# MCU.net
KiCad netlist of a schematic drawn in Altium Designer
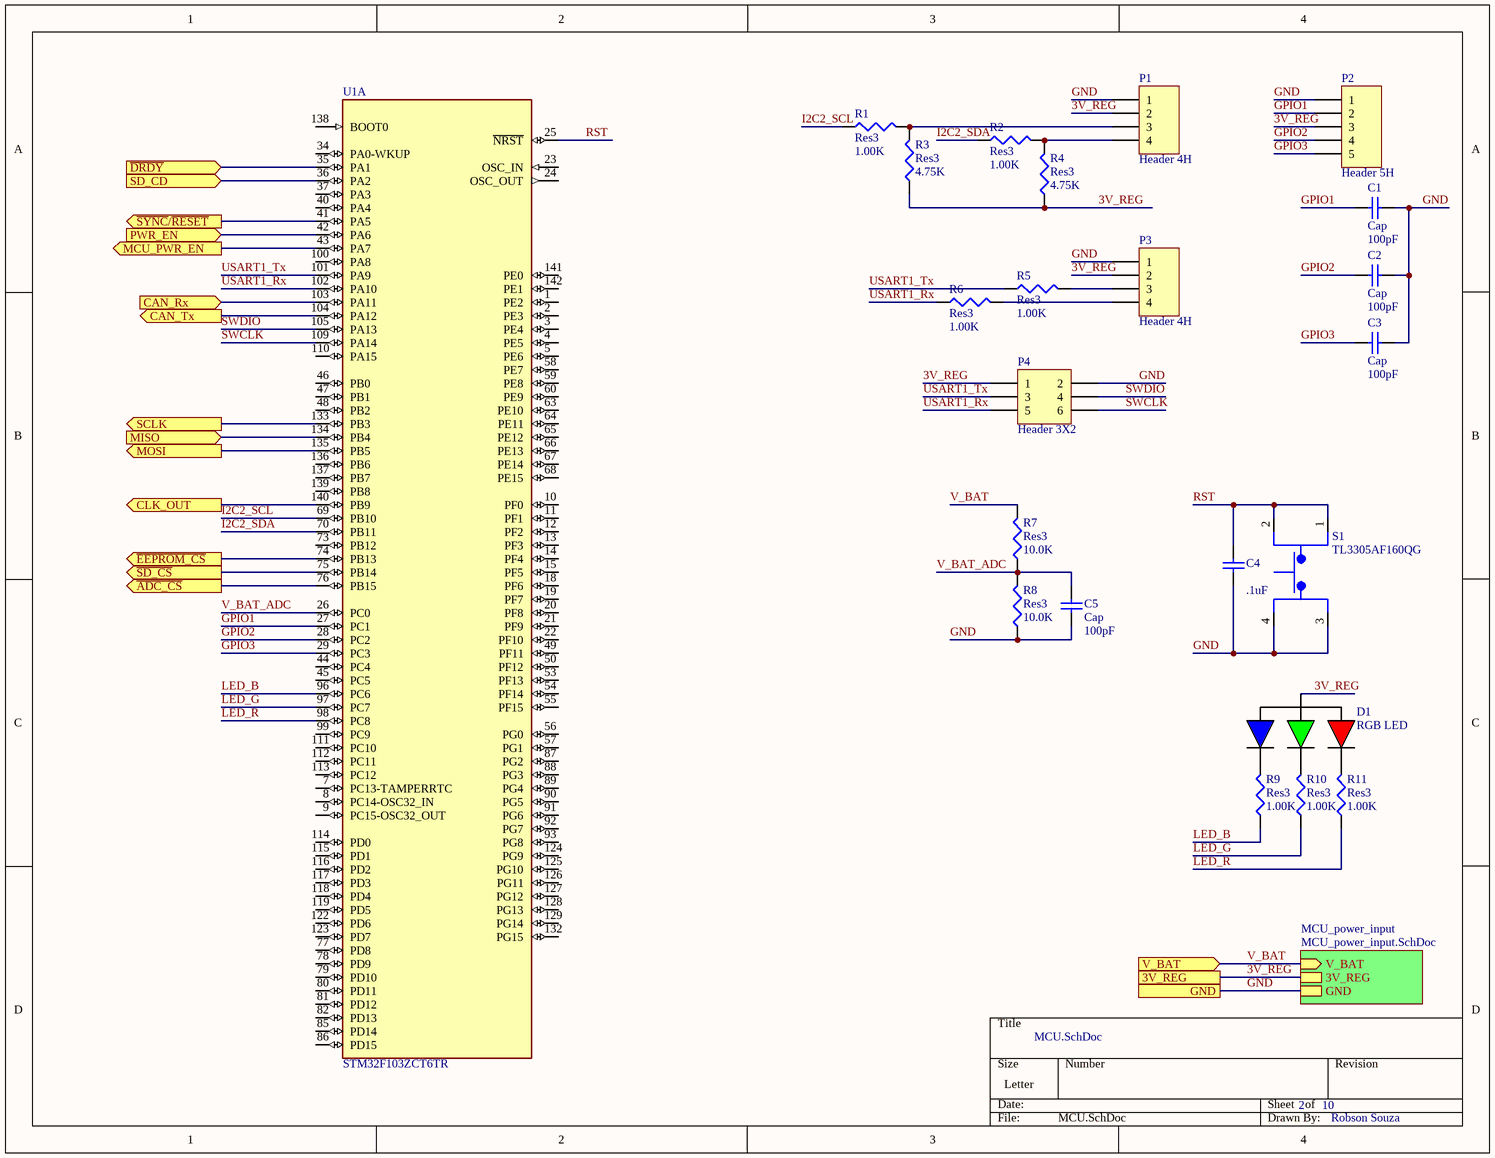
[diagram p0: MCU.SchDoc]

(export (version "E")
  (design (tool "Eeschema 10.0.6"))
  (components
    (comp (ref "C1")
      (value "Cap")
      (footprint "CAPC2012X09M")
      (description "CAP CER 100pF 500v COG 0805")
      (fields
        (field (name "ALTIUM_VALUE") "100pF")
        (field (name "TOLERANCE") "±5%")
        (field (name "MPN") "C0805C101JCGACTU")
      )
      (libsource (lib "esd_library") (part "CAP-COG-100pF-500V-±5%"))
    )
    (comp (ref "C2")
      (value "Cap")
      (footprint "CAPC2012X09M")
      (description "CAP CER 100pF 500v COG 0805")
      (fields
        (field (name "ALTIUM_VALUE") "100pF")
        (field (name "TOLERANCE") "±5%")
        (field (name "MPN") "C0805C101JCGACTU")
      )
      (libsource (lib "esd_library") (part "CAP-COG-100pF-500V-±5%"))
    )
    (comp (ref "C3")
      (value "Cap")
      (footprint "CAPC2012X09M")
      (description "CAP CER 100pF 500v COG 0805")
      (fields
        (field (name "ALTIUM_VALUE") "100pF")
        (field (name "TOLERANCE") "±5%")
        (field (name "MPN") "C0805C101JCGACTU")
      )
      (libsource (lib "esd_library") (part "CAP-COG-100pF-500V-±5%"))
    )
    (comp (ref "C4")
      (value ".1uF")
      (footprint "CAPC2012X09M")
      (description "CAP CER 50v X7R 0805")
      (fields (field (name "TOLERANCE") "±5%") (field (name "MPN") "C0805C104J5RACTU"))
      (libsource (lib "esd_library") (part "CAP-X7R-.1uF-50V-±5%"))
    )
    (comp (ref "C5")
      (value "Cap")
      (footprint "CAPC2012X09M")
      (description "CAP CER 100pF 500v COG 0805")
      (fields
        (field (name "ALTIUM_VALUE") "100pF")
        (field (name "TOLERANCE") "±5%")
        (field (name "MPN") "C0805C101JCGACTU")
      )
      (libsource (lib "esd_library") (part "CAP-COG-100pF-500V-±5%"))
    )
    (comp (ref "D1")
      (value "RGB LED")
      (footprint "SML-LX0303RGBC1TR")
      (fields (field (name "MP") "SML-LX0303RGBC/1TR"))
      (libsource (lib "SML-LX0303RGBC1TR") (part "SML-LX0303RGBC/1TR"))
    )
    (comp (ref "P1")
      (value "Header 4H")
      (footprint "HDR1X4H")
      (description "Header, 4-Pin, Right Angle")
      (fields (field (name "PUBLISHER") "Altium Limited"))
      (libsource (lib "Miscellaneous Connectors") (part "Header 4H"))
    )
    (comp (ref "P2")
      (value "Header 5H")
      (footprint "HDR1X5H")
      (description "Header, 5-Pin, Right Angle")
      (fields (field (name "PUBLISHER") "Altium Limited"))
      (libsource (lib "Miscellaneous Connectors") (part "Header 5H"))
    )
    (comp (ref "P3")
      (value "Header 4H")
      (footprint "HDR1X4H")
      (description "Header, 4-Pin, Right Angle")
      (fields (field (name "PUBLISHER") "Altium Limited"))
      (libsource (lib "Miscellaneous Connectors") (part "Header 4H"))
    )
    (comp (ref "P4")
      (value "Header 3X2")
      (footprint "HDR2X3")
      (description "Header, 3-Pin, Dual row")
      (fields (field (name "PUBLISHER") "Altium Limited"))
      (libsource (lib "Miscellaneous Connectors") (part "Header 3X2"))
    )
    (comp (ref "R1")
      (value "Res3")
      (footprint "RESC2112X05M")
      (description "RES SMD 1.00K OHM 1% 1/8W 0805")
      (fields (field (name "ALTIUM_VALUE") "1.00K") (field (name "MPN") "CRCW08051K00FKEA"))
      (libsource (lib "esd_library") (part "Resistor_1.00K"))
    )
    (comp (ref "R2")
      (value "Res3")
      (footprint "RESC2112X05M")
      (description "RES SMD 1.00K OHM 1% 1/8W 0805")
      (fields (field (name "ALTIUM_VALUE") "1.00K") (field (name "MPN") "CRCW08051K00FKEA"))
      (libsource (lib "esd_library") (part "Resistor_1.00K"))
    )
    (comp (ref "R3")
      (value "Res3")
      (footprint "RESC2112X05M")
      (description "RES SMD 4.75K OHM 1% 1/8W 0805")
      (fields (field (name "ALTIUM_VALUE") "4.75K") (field (name "MPN") "CRCW08054K75FKEA"))
      (libsource (lib "esd_library") (part "Resistor_4.75K"))
    )
    (comp (ref "R4")
      (value "Res3")
      (footprint "RESC2112X05M")
      (description "RES SMD 4.75K OHM 1% 1/8W 0805")
      (fields (field (name "ALTIUM_VALUE") "4.75K") (field (name "MPN") "CRCW08054K75FKEA"))
      (libsource (lib "esd_library") (part "Resistor_4.75K"))
    )
    (comp (ref "R5")
      (value "Res3")
      (footprint "RESC2112X05M")
      (description "RES SMD 1.00K OHM 1% 1/8W 0805")
      (fields (field (name "ALTIUM_VALUE") "1.00K") (field (name "MPN") "CRCW08051K00FKEA"))
      (libsource (lib "esd_library") (part "Resistor_1.00K"))
    )
    (comp (ref "R6")
      (value "Res3")
      (footprint "RESC2112X05M")
      (description "RES SMD 1.00K OHM 1% 1/8W 0805")
      (fields (field (name "ALTIUM_VALUE") "1.00K") (field (name "MPN") "CRCW08051K00FKEA"))
      (libsource (lib "esd_library") (part "Resistor_1.00K"))
    )
    (comp (ref "R7")
      (value "Res3")
      (footprint "RESC2112X05M")
      (description "RES SMD 10.0K OHM 1% 1/8W 0805")
      (fields (field (name "ALTIUM_VALUE") "10.0K") (field (name "MPN") "CRCW080510K0FKEA"))
      (libsource (lib "esd_library") (part "Resistor_10.0K"))
    )
    (comp (ref "R8")
      (value "Res3")
      (footprint "RESC2112X05M")
      (description "RES SMD 10.0K OHM 1% 1/8W 0805")
      (fields (field (name "ALTIUM_VALUE") "10.0K") (field (name "MPN") "CRCW080510K0FKEA"))
      (libsource (lib "esd_library") (part "Resistor_10.0K"))
    )
    (comp (ref "R9")
      (value "Res3")
      (footprint "RESC2112X05M")
      (description "RES SMD 1.00K OHM 1% 1/8W 0805")
      (fields (field (name "ALTIUM_VALUE") "1.00K") (field (name "MPN") "CRCW08051K00FKEA"))
      (libsource (lib "esd_library") (part "Resistor_1.00K"))
    )
    (comp (ref "R10")
      (value "Res3")
      (footprint "RESC2112X05M")
      (description "RES SMD 1.00K OHM 1% 1/8W 0805")
      (fields (field (name "ALTIUM_VALUE") "1.00K") (field (name "MPN") "CRCW08051K00FKEA"))
      (libsource (lib "esd_library") (part "Resistor_1.00K"))
    )
    (comp (ref "R11")
      (value "Res3")
      (footprint "RESC2112X05M")
      (description "RES SMD 1.00K OHM 1% 1/8W 0805")
      (fields (field (name "ALTIUM_VALUE") "1.00K") (field (name "MPN") "CRCW08051K00FKEA"))
      (libsource (lib "esd_library") (part "Resistor_1.00K"))
    )
    (comp (ref "S1")
      (value "TL3305AF160QG")
      (footprint "SW_TL3305AF160QG")
      (description "Tactile Switch SPST-NO Top Actuated Surface Mount")
      (fields (field (name "MF") "E-Switch"))
      (libsource (lib "TL3305AF160QG") (part "TL3305AF160QG"))
    )
    (comp (ref "U1")
      (value "STM32F103ZCT6TR")
      (footprint "QFP50P2200X2200X160-144N")
      (fields (field (name "DIGI-KEY_PART_NUMBER") "497-18761-2-ND") (field (name "MF") "STMicroelectronics"))
      (libsource (lib "STM32F103ZCT6TR") (part "STM32F103ZCT6TR"))
    )
  )
  (nets
    (net (code "1") (name "/3V_REG") (class "Default")
      (node (ref "D1") (pin "1") (pinfunction "1_1") (pintype "passive"))
      (node (ref "P1") (pin "2") (pinfunction "2_2") (pintype "passive"))
      (node (ref "P2") (pin "3") (pinfunction "3_3") (pintype "passive"))
      (node (ref "P3") (pin "2") (pinfunction "2_2") (pintype "passive"))
      (node (ref "P4") (pin "1") (pinfunction "1_1") (pintype "passive"))
      (node (ref "R3") (pin "1") (pinfunction "1_1") (pintype "passive"))
      (node (ref "R4") (pin "1") (pinfunction "1_1") (pintype "passive"))
    )
    (net (code "2") (name "/CAN_Rx") (class "Default")
      (node (ref "U1") (pin "103") (pinfunction "PA11_103") (pintype "bidirectional"))
    )
    (net (code "3") (name "/CAN_Tx") (class "Default")
      (node (ref "U1") (pin "104") (pinfunction "PA12_104") (pintype "bidirectional"))
    )
    (net (code "4") (name "/CLK_OUT") (class "Default")
      (node (ref "U1") (pin "140") (pinfunction "PB9_140") (pintype "bidirectional"))
    )
    (net (code "5") (name "/GND") (class "Default")
      (node (ref "C1") (pin "1") (pinfunction "1_1") (pintype "passive"))
      (node (ref "C2") (pin "1") (pinfunction "1_1") (pintype "passive"))
      (node (ref "C3") (pin "1") (pinfunction "1_1") (pintype "passive"))
      (node (ref "C4") (pin "1") (pinfunction "1_1") (pintype "passive"))
      (node (ref "C5") (pin "1") (pinfunction "1_1") (pintype "passive"))
      (node (ref "P1") (pin "1") (pinfunction "1_1") (pintype "passive"))
      (node (ref "P2") (pin "1") (pinfunction "1_1") (pintype "passive"))
      (node (ref "P3") (pin "1") (pinfunction "1_1") (pintype "passive"))
      (node (ref "P4") (pin "2") (pinfunction "2_2") (pintype "passive"))
      (node (ref "R8") (pin "1") (pinfunction "1_1") (pintype "passive"))
      (node (ref "S1") (pin "3") (pinfunction "3_3") (pintype "passive"))
      (node (ref "S1") (pin "4") (pinfunction "4_4") (pintype "passive"))
    )
    (net (code "6") (name "/GPIO1") (class "Default")
      (node (ref "C1") (pin "2") (pinfunction "2_2") (pintype "passive"))
      (node (ref "P2") (pin "2") (pinfunction "2_2") (pintype "passive"))
      (node (ref "U1") (pin "27") (pinfunction "PC1_27") (pintype "bidirectional"))
    )
    (net (code "7") (name "/GPIO2") (class "Default")
      (node (ref "C2") (pin "2") (pinfunction "2_2") (pintype "passive"))
      (node (ref "P2") (pin "4") (pinfunction "4_4") (pintype "passive"))
      (node (ref "U1") (pin "28") (pinfunction "PC2_28") (pintype "bidirectional"))
    )
    (net (code "8") (name "/GPIO3") (class "Default")
      (node (ref "C3") (pin "2") (pinfunction "2_2") (pintype "passive"))
      (node (ref "P2") (pin "5") (pinfunction "5_5") (pintype "passive"))
      (node (ref "U1") (pin "29") (pinfunction "PC3_29") (pintype "bidirectional"))
    )
    (net (code "9") (name "/I2C2_SCL") (class "Default")
      (node (ref "R1") (pin "1") (pinfunction "1_1") (pintype "passive"))
      (node (ref "U1") (pin "69") (pinfunction "PB10_69") (pintype "bidirectional"))
    )
    (net (code "10") (name "/I2C2_SDA") (class "Default")
      (node (ref "R2") (pin "1") (pinfunction "1_1") (pintype "passive"))
      (node (ref "U1") (pin "70") (pinfunction "PB11_70") (pintype "bidirectional"))
    )
    (net (code "11") (name "/LED_B") (class "Default")
      (node (ref "R9") (pin "1") (pinfunction "1_1") (pintype "passive"))
      (node (ref "U1") (pin "96") (pinfunction "PC6_96") (pintype "bidirectional"))
    )
    (net (code "12") (name "/LED_G") (class "Default")
      (node (ref "R10") (pin "1") (pinfunction "1_1") (pintype "passive"))
      (node (ref "U1") (pin "97") (pinfunction "PC7_97") (pintype "bidirectional"))
    )
    (net (code "13") (name "/LED_R") (class "Default")
      (node (ref "R11") (pin "1") (pinfunction "1_1") (pintype "passive"))
      (node (ref "U1") (pin "98") (pinfunction "PC8_98") (pintype "bidirectional"))
    )
    (net (code "14") (name "/MCU_PWR_EN") (class "Default")
      (node (ref "U1") (pin "43") (pinfunction "PA7_43") (pintype "bidirectional"))
    )
    (net (code "15") (name "/MISO") (class "Default")
      (node (ref "U1") (pin "134") (pinfunction "PB4_134") (pintype "bidirectional"))
    )
    (net (code "16") (name "/MOSI") (class "Default")
      (node (ref "U1") (pin "135") (pinfunction "PB5_135") (pintype "bidirectional"))
    )
    (net (code "17") (name "/PWR_EN") (class "Default")
      (node (ref "U1") (pin "42") (pinfunction "PA6_42") (pintype "bidirectional"))
    )
    (net (code "18") (name "/RST") (class "Default")
      (node (ref "C4") (pin "2") (pinfunction "2_2") (pintype "passive"))
      (node (ref "S1") (pin "1") (pinfunction "1_1") (pintype "passive"))
      (node (ref "S1") (pin "2") (pinfunction "2_2") (pintype "passive"))
      (node (ref "U1") (pin "25") (pinfunction "~{NRST}_25") (pintype "bidirectional"))
    )
    (net (code "19") (name "/SCLK") (class "Default")
      (node (ref "U1") (pin "133") (pinfunction "PB3_133") (pintype "bidirectional"))
    )
    (net (code "20") (name "/SD_CD") (class "Default")
      (node (ref "U1") (pin "36") (pinfunction "PA2_36") (pintype "bidirectional"))
    )
    (net (code "21") (name "/SWCLK") (class "Default")
      (node (ref "P4") (pin "6") (pinfunction "6_6") (pintype "passive"))
      (node (ref "U1") (pin "109") (pinfunction "PA14_109") (pintype "bidirectional"))
    )
    (net (code "22") (name "/SWDIO") (class "Default")
      (node (ref "P4") (pin "4") (pinfunction "4_4") (pintype "passive"))
      (node (ref "U1") (pin "105") (pinfunction "PA13_105") (pintype "bidirectional"))
    )
    (net (code "23") (name "/USART1_Rx") (class "Default")
      (node (ref "P4") (pin "5") (pinfunction "5_5") (pintype "passive"))
      (node (ref "R6") (pin "1") (pinfunction "1_1") (pintype "passive"))
      (node (ref "U1") (pin "102") (pinfunction "PA10_102") (pintype "bidirectional"))
    )
    (net (code "24") (name "/USART1_Tx") (class "Default")
      (node (ref "P4") (pin "3") (pinfunction "3_3") (pintype "passive"))
      (node (ref "R5") (pin "1") (pinfunction "1_1") (pintype "passive"))
      (node (ref "U1") (pin "101") (pinfunction "PA9_101") (pintype "bidirectional"))
    )
    (net (code "25") (name "/V_BAT") (class "Default")
      (node (ref "R7") (pin "2") (pinfunction "2_2") (pintype "passive"))
    )
    (net (code "26") (name "/V_BAT_ADC") (class "Default")
      (node (ref "C5") (pin "2") (pinfunction "2_2") (pintype "passive"))
      (node (ref "R7") (pin "1") (pinfunction "1_1") (pintype "passive"))
      (node (ref "R8") (pin "2") (pinfunction "2_2") (pintype "passive"))
      (node (ref "U1") (pin "26") (pinfunction "PC0_26") (pintype "bidirectional"))
    )
    (net (code "27") (name "/~{ADC_CS}") (class "Default")
      (node (ref "U1") (pin "76") (pinfunction "PB15_76") (pintype "bidirectional"))
    )
    (net (code "28") (name "/~{DRDY}") (class "Default")
      (node (ref "U1") (pin "35") (pinfunction "PA1_35") (pintype "bidirectional"))
    )
    (net (code "29") (name "/~{EEPROM_CS}") (class "Default")
      (node (ref "U1") (pin "74") (pinfunction "PB13_74") (pintype "bidirectional"))
    )
    (net (code "30") (name "/~{SD_CS}") (class "Default")
      (node (ref "U1") (pin "75") (pinfunction "PB14_75") (pintype "bidirectional"))
    )
    (net (code "31") (name "/~{SYNC}{slash}~{RESET}") (class "Default")
      (node (ref "U1") (pin "41") (pinfunction "PA5_41") (pintype "bidirectional"))
    )
    (net (code "32") (name "Net-(D1-Pad2)") (class "Default")
      (node (ref "D1") (pin "2") (pinfunction "2_2") (pintype "passive"))
      (node (ref "R11") (pin "2") (pinfunction "2_2") (pintype "passive"))
    )
    (net (code "33") (name "Net-(D1-Pad3)") (class "Default")
      (node (ref "D1") (pin "3") (pinfunction "3_3") (pintype "passive"))
      (node (ref "R10") (pin "2") (pinfunction "2_2") (pintype "passive"))
    )
    (net (code "34") (name "Net-(D1-Pad4)") (class "Default")
      (node (ref "D1") (pin "4") (pinfunction "4_4") (pintype "passive"))
      (node (ref "R9") (pin "2") (pinfunction "2_2") (pintype "passive"))
    )
    (net (code "35") (name "Net-(P1-Pad3)") (class "Default")
      (node (ref "P1") (pin "3") (pinfunction "3_3") (pintype "passive"))
      (node (ref "R1") (pin "2") (pinfunction "2_2") (pintype "passive"))
      (node (ref "R3") (pin "2") (pinfunction "2_2") (pintype "passive"))
    )
    (net (code "36") (name "Net-(P1-Pad4)") (class "Default")
      (node (ref "P1") (pin "4") (pinfunction "4_4") (pintype "passive"))
      (node (ref "R2") (pin "2") (pinfunction "2_2") (pintype "passive"))
      (node (ref "R4") (pin "2") (pinfunction "2_2") (pintype "passive"))
    )
    (net (code "37") (name "Net-(P3-Pad3)") (class "Default")
      (node (ref "P3") (pin "3") (pinfunction "3_3") (pintype "passive"))
      (node (ref "R5") (pin "2") (pinfunction "2_2") (pintype "passive"))
    )
    (net (code "38") (name "Net-(P3-Pad4)") (class "Default")
      (node (ref "P3") (pin "4") (pinfunction "4_4") (pintype "passive"))
      (node (ref "R6") (pin "2") (pinfunction "2_2") (pintype "passive"))
    )
    (net (code "39") (name "unconnected-(U1A-BOOT0-Pad138)") (class "Default")
      (node (ref "U1") (pin "138") (pinfunction "BOOT0_138") (pintype "input"))
    )
    (net (code "40") (name "unconnected-(U1A-OSC_IN-Pad23)") (class "Default")
      (node (ref "U1") (pin "23") (pinfunction "OSC_IN_23") (pintype "input"))
    )
    (net (code "41") (name "unconnected-(U1A-OSC_OUT-Pad24)") (class "Default")
      (node (ref "U1") (pin "24") (pinfunction "OSC_OUT_24") (pintype "output"))
    )
    (net (code "42") (name "unconnected-(U1A-PA0-WKUP-Pad34)") (class "Default")
      (node (ref "U1") (pin "34") (pinfunction "PA0-WKUP_34") (pintype "bidirectional"))
    )
    (net (code "43") (name "unconnected-(U1A-PA3-Pad37)") (class "Default")
      (node (ref "U1") (pin "37") (pinfunction "PA3_37") (pintype "bidirectional"))
    )
    (net (code "44") (name "unconnected-(U1A-PA4-Pad40)") (class "Default")
      (node (ref "U1") (pin "40") (pinfunction "PA4_40") (pintype "bidirectional"))
    )
    (net (code "45") (name "unconnected-(U1A-PA8-Pad100)") (class "Default")
      (node (ref "U1") (pin "100") (pinfunction "PA8_100") (pintype "bidirectional"))
    )
    (net (code "46") (name "unconnected-(U1A-PA15-Pad110)") (class "Default")
      (node (ref "U1") (pin "110") (pinfunction "PA15_110") (pintype "bidirectional"))
    )
    (net (code "47") (name "unconnected-(U1A-PB0-Pad46)") (class "Default")
      (node (ref "U1") (pin "46") (pinfunction "PB0_46") (pintype "bidirectional"))
    )
    (net (code "48") (name "unconnected-(U1A-PB1-Pad47)") (class "Default")
      (node (ref "U1") (pin "47") (pinfunction "PB1_47") (pintype "bidirectional"))
    )
    (net (code "49") (name "unconnected-(U1A-PB2-Pad48)") (class "Default")
      (node (ref "U1") (pin "48") (pinfunction "PB2_48") (pintype "bidirectional"))
    )
    (net (code "50") (name "unconnected-(U1A-PB6-Pad136)") (class "Default")
      (node (ref "U1") (pin "136") (pinfunction "PB6_136") (pintype "bidirectional"))
    )
    (net (code "51") (name "unconnected-(U1A-PB7-Pad137)") (class "Default")
      (node (ref "U1") (pin "137") (pinfunction "PB7_137") (pintype "bidirectional"))
    )
    (net (code "52") (name "unconnected-(U1A-PB8-Pad139)") (class "Default")
      (node (ref "U1") (pin "139") (pinfunction "PB8_139") (pintype "bidirectional"))
    )
    (net (code "53") (name "unconnected-(U1A-PB12-Pad73)") (class "Default")
      (node (ref "U1") (pin "73") (pinfunction "PB12_73") (pintype "bidirectional"))
    )
    (net (code "54") (name "unconnected-(U1A-PC4-Pad44)") (class "Default")
      (node (ref "U1") (pin "44") (pinfunction "PC4_44") (pintype "bidirectional"))
    )
    (net (code "55") (name "unconnected-(U1A-PC5-Pad45)") (class "Default")
      (node (ref "U1") (pin "45") (pinfunction "PC5_45") (pintype "bidirectional"))
    )
    (net (code "56") (name "unconnected-(U1A-PC9-Pad99)") (class "Default")
      (node (ref "U1") (pin "99") (pinfunction "PC9_99") (pintype "bidirectional"))
    )
    (net (code "57") (name "unconnected-(U1A-PC10-Pad111)") (class "Default")
      (node (ref "U1") (pin "111") (pinfunction "PC10_111") (pintype "bidirectional"))
    )
    (net (code "58") (name "unconnected-(U1A-PC11-Pad112)") (class "Default")
      (node (ref "U1") (pin "112") (pinfunction "PC11_112") (pintype "bidirectional"))
    )
    (net (code "59") (name "unconnected-(U1A-PC12-Pad113)") (class "Default")
      (node (ref "U1") (pin "113") (pinfunction "PC12_113") (pintype "bidirectional"))
    )
    (net (code "60") (name "unconnected-(U1A-PC13-TAMPERRTC-Pad7)") (class "Default")
      (node (ref "U1") (pin "7") (pinfunction "PC13-TAMPERRTC_7") (pintype "bidirectional"))
    )
    (net (code "61") (name "unconnected-(U1A-PC14-OSC32_IN-Pad8)") (class "Default")
      (node (ref "U1") (pin "8") (pinfunction "PC14-OSC32_IN_8") (pintype "bidirectional"))
    )
    (net (code "62") (name "unconnected-(U1A-PC15-OSC32_OUT-Pad9)") (class "Default")
      (node (ref "U1") (pin "9") (pinfunction "PC15-OSC32_OUT_9") (pintype "bidirectional"))
    )
    (net (code "63") (name "unconnected-(U1A-PD0-Pad114)") (class "Default")
      (node (ref "U1") (pin "114") (pinfunction "PD0_114") (pintype "bidirectional"))
    )
    (net (code "64") (name "unconnected-(U1A-PD1-Pad115)") (class "Default")
      (node (ref "U1") (pin "115") (pinfunction "PD1_115") (pintype "bidirectional"))
    )
    (net (code "65") (name "unconnected-(U1A-PD2-Pad116)") (class "Default")
      (node (ref "U1") (pin "116") (pinfunction "PD2_116") (pintype "bidirectional"))
    )
    (net (code "66") (name "unconnected-(U1A-PD3-Pad117)") (class "Default")
      (node (ref "U1") (pin "117") (pinfunction "PD3_117") (pintype "bidirectional"))
    )
    (net (code "67") (name "unconnected-(U1A-PD4-Pad118)") (class "Default")
      (node (ref "U1") (pin "118") (pinfunction "PD4_118") (pintype "bidirectional"))
    )
    (net (code "68") (name "unconnected-(U1A-PD5-Pad119)") (class "Default")
      (node (ref "U1") (pin "119") (pinfunction "PD5_119") (pintype "bidirectional"))
    )
    (net (code "69") (name "unconnected-(U1A-PD6-Pad122)") (class "Default")
      (node (ref "U1") (pin "122") (pinfunction "PD6_122") (pintype "bidirectional"))
    )
    (net (code "70") (name "unconnected-(U1A-PD7-Pad123)") (class "Default")
      (node (ref "U1") (pin "123") (pinfunction "PD7_123") (pintype "bidirectional"))
    )
    (net (code "71") (name "unconnected-(U1A-PD8-Pad77)") (class "Default")
      (node (ref "U1") (pin "77") (pinfunction "PD8_77") (pintype "bidirectional"))
    )
    (net (code "72") (name "unconnected-(U1A-PD9-Pad78)") (class "Default")
      (node (ref "U1") (pin "78") (pinfunction "PD9_78") (pintype "bidirectional"))
    )
    (net (code "73") (name "unconnected-(U1A-PD10-Pad79)") (class "Default")
      (node (ref "U1") (pin "79") (pinfunction "PD10_79") (pintype "bidirectional"))
    )
    (net (code "74") (name "unconnected-(U1A-PD11-Pad80)") (class "Default")
      (node (ref "U1") (pin "80") (pinfunction "PD11_80") (pintype "bidirectional"))
    )
    (net (code "75") (name "unconnected-(U1A-PD12-Pad81)") (class "Default")
      (node (ref "U1") (pin "81") (pinfunction "PD12_81") (pintype "bidirectional"))
    )
    (net (code "76") (name "unconnected-(U1A-PD13-Pad82)") (class "Default")
      (node (ref "U1") (pin "82") (pinfunction "PD13_82") (pintype "bidirectional"))
    )
    (net (code "77") (name "unconnected-(U1A-PD14-Pad85)") (class "Default")
      (node (ref "U1") (pin "85") (pinfunction "PD14_85") (pintype "bidirectional"))
    )
    (net (code "78") (name "unconnected-(U1A-PD15-Pad86)") (class "Default")
      (node (ref "U1") (pin "86") (pinfunction "PD15_86") (pintype "bidirectional"))
    )
    (net (code "79") (name "unconnected-(U1A-PE0-Pad141)") (class "Default")
      (node (ref "U1") (pin "141") (pinfunction "PE0_141") (pintype "bidirectional"))
    )
    (net (code "80") (name "unconnected-(U1A-PE1-Pad142)") (class "Default")
      (node (ref "U1") (pin "142") (pinfunction "PE1_142") (pintype "bidirectional"))
    )
    (net (code "81") (name "unconnected-(U1A-PE2-Pad1)") (class "Default")
      (node (ref "U1") (pin "1") (pinfunction "PE2_1") (pintype "bidirectional"))
    )
    (net (code "82") (name "unconnected-(U1A-PE3-Pad2)") (class "Default")
      (node (ref "U1") (pin "2") (pinfunction "PE3_2") (pintype "bidirectional"))
    )
    (net (code "83") (name "unconnected-(U1A-PE4-Pad3)") (class "Default")
      (node (ref "U1") (pin "3") (pinfunction "PE4_3") (pintype "bidirectional"))
    )
    (net (code "84") (name "unconnected-(U1A-PE5-Pad4)") (class "Default")
      (node (ref "U1") (pin "4") (pinfunction "PE5_4") (pintype "bidirectional"))
    )
    (net (code "85") (name "unconnected-(U1A-PE6-Pad5)") (class "Default")
      (node (ref "U1") (pin "5") (pinfunction "PE6_5") (pintype "bidirectional"))
    )
    (net (code "86") (name "unconnected-(U1A-PE7-Pad58)") (class "Default")
      (node (ref "U1") (pin "58") (pinfunction "PE7_58") (pintype "bidirectional"))
    )
    (net (code "87") (name "unconnected-(U1A-PE8-Pad59)") (class "Default")
      (node (ref "U1") (pin "59") (pinfunction "PE8_59") (pintype "bidirectional"))
    )
    (net (code "88") (name "unconnected-(U1A-PE9-Pad60)") (class "Default")
      (node (ref "U1") (pin "60") (pinfunction "PE9_60") (pintype "bidirectional"))
    )
    (net (code "89") (name "unconnected-(U1A-PE10-Pad63)") (class "Default")
      (node (ref "U1") (pin "63") (pinfunction "PE10_63") (pintype "bidirectional"))
    )
    (net (code "90") (name "unconnected-(U1A-PE11-Pad64)") (class "Default")
      (node (ref "U1") (pin "64") (pinfunction "PE11_64") (pintype "bidirectional"))
    )
    (net (code "91") (name "unconnected-(U1A-PE12-Pad65)") (class "Default")
      (node (ref "U1") (pin "65") (pinfunction "PE12_65") (pintype "bidirectional"))
    )
    (net (code "92") (name "unconnected-(U1A-PE13-Pad66)") (class "Default")
      (node (ref "U1") (pin "66") (pinfunction "PE13_66") (pintype "bidirectional"))
    )
    (net (code "93") (name "unconnected-(U1A-PE14-Pad67)") (class "Default")
      (node (ref "U1") (pin "67") (pinfunction "PE14_67") (pintype "bidirectional"))
    )
    (net (code "94") (name "unconnected-(U1A-PE15-Pad68)") (class "Default")
      (node (ref "U1") (pin "68") (pinfunction "PE15_68") (pintype "bidirectional"))
    )
    (net (code "95") (name "unconnected-(U1A-PF0-Pad10)") (class "Default")
      (node (ref "U1") (pin "10") (pinfunction "PF0_10") (pintype "bidirectional"))
    )
    (net (code "96") (name "unconnected-(U1A-PF1-Pad11)") (class "Default")
      (node (ref "U1") (pin "11") (pinfunction "PF1_11") (pintype "bidirectional"))
    )
    (net (code "97") (name "unconnected-(U1A-PF2-Pad12)") (class "Default")
      (node (ref "U1") (pin "12") (pinfunction "PF2_12") (pintype "bidirectional"))
    )
    (net (code "98") (name "unconnected-(U1A-PF3-Pad13)") (class "Default")
      (node (ref "U1") (pin "13") (pinfunction "PF3_13") (pintype "bidirectional"))
    )
    (net (code "99") (name "unconnected-(U1A-PF4-Pad14)") (class "Default")
      (node (ref "U1") (pin "14") (pinfunction "PF4_14") (pintype "bidirectional"))
    )
    (net (code "100") (name "unconnected-(U1A-PF5-Pad15)") (class "Default")
      (node (ref "U1") (pin "15") (pinfunction "PF5_15") (pintype "bidirectional"))
    )
    (net (code "101") (name "unconnected-(U1A-PF6-Pad18)") (class "Default")
      (node (ref "U1") (pin "18") (pinfunction "PF6_18") (pintype "bidirectional"))
    )
    (net (code "102") (name "unconnected-(U1A-PF7-Pad19)") (class "Default")
      (node (ref "U1") (pin "19") (pinfunction "PF7_19") (pintype "bidirectional"))
    )
    (net (code "103") (name "unconnected-(U1A-PF8-Pad20)") (class "Default")
      (node (ref "U1") (pin "20") (pinfunction "PF8_20") (pintype "bidirectional"))
    )
    (net (code "104") (name "unconnected-(U1A-PF9-Pad21)") (class "Default")
      (node (ref "U1") (pin "21") (pinfunction "PF9_21") (pintype "bidirectional"))
    )
    (net (code "105") (name "unconnected-(U1A-PF10-Pad22)") (class "Default")
      (node (ref "U1") (pin "22") (pinfunction "PF10_22") (pintype "bidirectional"))
    )
    (net (code "106") (name "unconnected-(U1A-PF11-Pad49)") (class "Default")
      (node (ref "U1") (pin "49") (pinfunction "PF11_49") (pintype "bidirectional"))
    )
    (net (code "107") (name "unconnected-(U1A-PF12-Pad50)") (class "Default")
      (node (ref "U1") (pin "50") (pinfunction "PF12_50") (pintype "bidirectional"))
    )
    (net (code "108") (name "unconnected-(U1A-PF13-Pad53)") (class "Default")
      (node (ref "U1") (pin "53") (pinfunction "PF13_53") (pintype "bidirectional"))
    )
    (net (code "109") (name "unconnected-(U1A-PF14-Pad54)") (class "Default")
      (node (ref "U1") (pin "54") (pinfunction "PF14_54") (pintype "bidirectional"))
    )
    (net (code "110") (name "unconnected-(U1A-PF15-Pad55)") (class "Default")
      (node (ref "U1") (pin "55") (pinfunction "PF15_55") (pintype "bidirectional"))
    )
    (net (code "111") (name "unconnected-(U1A-PG0-Pad56)") (class "Default")
      (node (ref "U1") (pin "56") (pinfunction "PG0_56") (pintype "bidirectional"))
    )
    (net (code "112") (name "unconnected-(U1A-PG1-Pad57)") (class "Default")
      (node (ref "U1") (pin "57") (pinfunction "PG1_57") (pintype "bidirectional"))
    )
    (net (code "113") (name "unconnected-(U1A-PG2-Pad87)") (class "Default")
      (node (ref "U1") (pin "87") (pinfunction "PG2_87") (pintype "bidirectional"))
    )
    (net (code "114") (name "unconnected-(U1A-PG3-Pad88)") (class "Default")
      (node (ref "U1") (pin "88") (pinfunction "PG3_88") (pintype "bidirectional"))
    )
    (net (code "115") (name "unconnected-(U1A-PG4-Pad89)") (class "Default")
      (node (ref "U1") (pin "89") (pinfunction "PG4_89") (pintype "bidirectional"))
    )
    (net (code "116") (name "unconnected-(U1A-PG5-Pad90)") (class "Default")
      (node (ref "U1") (pin "90") (pinfunction "PG5_90") (pintype "bidirectional"))
    )
    (net (code "117") (name "unconnected-(U1A-PG6-Pad91)") (class "Default")
      (node (ref "U1") (pin "91") (pinfunction "PG6_91") (pintype "bidirectional"))
    )
    (net (code "118") (name "unconnected-(U1A-PG7-Pad92)") (class "Default")
      (node (ref "U1") (pin "92") (pinfunction "PG7_92") (pintype "bidirectional"))
    )
    (net (code "119") (name "unconnected-(U1A-PG8-Pad93)") (class "Default")
      (node (ref "U1") (pin "93") (pinfunction "PG8_93") (pintype "bidirectional"))
    )
    (net (code "120") (name "unconnected-(U1A-PG9-Pad124)") (class "Default")
      (node (ref "U1") (pin "124") (pinfunction "PG9_124") (pintype "bidirectional"))
    )
    (net (code "121") (name "unconnected-(U1A-PG10-Pad125)") (class "Default")
      (node (ref "U1") (pin "125") (pinfunction "PG10_125") (pintype "bidirectional"))
    )
    (net (code "122") (name "unconnected-(U1A-PG11-Pad126)") (class "Default")
      (node (ref "U1") (pin "126") (pinfunction "PG11_126") (pintype "bidirectional"))
    )
    (net (code "123") (name "unconnected-(U1A-PG12-Pad127)") (class "Default")
      (node (ref "U1") (pin "127") (pinfunction "PG12_127") (pintype "bidirectional"))
    )
    (net (code "124") (name "unconnected-(U1A-PG13-Pad128)") (class "Default")
      (node (ref "U1") (pin "128") (pinfunction "PG13_128") (pintype "bidirectional"))
    )
    (net (code "125") (name "unconnected-(U1A-PG14-Pad129)") (class "Default")
      (node (ref "U1") (pin "129") (pinfunction "PG14_129") (pintype "bidirectional"))
    )
    (net (code "126") (name "unconnected-(U1A-PG15-Pad132)") (class "Default")
      (node (ref "U1") (pin "132") (pinfunction "PG15_132") (pintype "bidirectional"))
    )
  )
)
